# Schematic__2024_schema_2024-06-13.net
KiCad netlist of a schematic drawn in EasyEDA
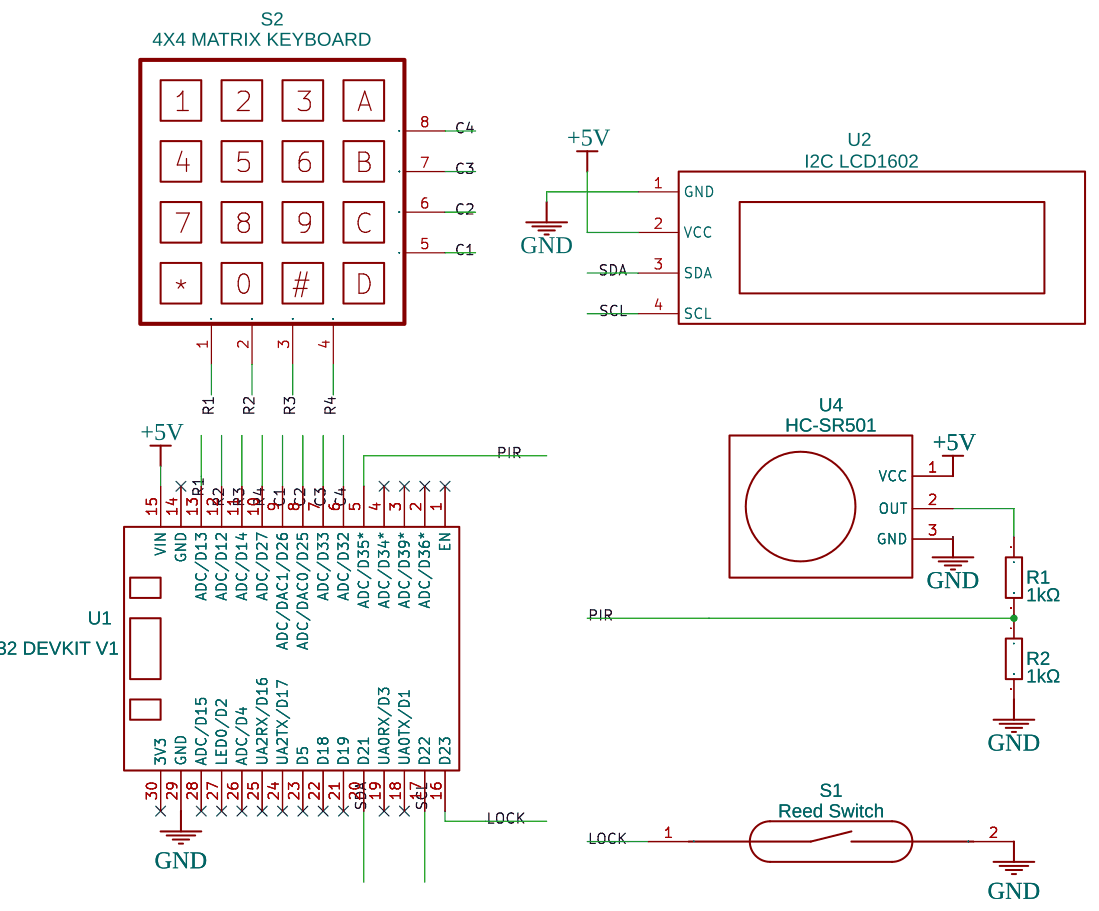
[diagram p0: schematic sheet]

(export (version "E")
  (design (tool "Eeschema 10.0.6"))
  (components
    (comp (ref "R1")
      (value "1kΩ")
      (fields
        (field (name "Manufacturer Part") "MBE04140C1001FC100")
        (field (name "Manufacturer") "VISHAY(威世)")
      )
      (libsource (lib "") (part "MBE04140C1001FC 100"))
    )
    (comp (ref "R2")
      (value "1kΩ")
      (fields
        (field (name "Manufacturer Part") "MBE04140C1001FC100")
        (field (name "Manufacturer") "VISHAY(威世)")
      )
      (libsource (lib "") (part "MBE04140C1001FC 100"))
    )
    (comp (ref "S1") (value "Reed Switch") (libsource (lib "") (part "Reed Switch")))
    (comp (ref "S2") (value "4X4 MATRIX KEYBOARD") (libsource (lib "") (part "4X4 MATRIX KEYBOARD")))
    (comp (ref "U1") (value "ESP32 DEVKIT V1") (libsource (lib "") (part "ESP32 DEVKIT V1")))
    (comp (ref "U2") (value "I2C LCD1602") (libsource (lib "") (part "I2C LCD1602")))
    (comp (ref "U4") (value "HC-SR501") (libsource (lib "") (part "HC-SR501")))
  )
  (nets
    (net (code "1") (name "+5V") (class "Default")
      (node (ref "U1") (pin "15") (pinfunction "VIN_15") (pintype "input"))
      (node (ref "U2") (pin "2") (pinfunction "VCC_2") (pintype "unspecified"))
      (node (ref "U4") (pin "1") (pinfunction "VCC_1") (pintype "unspecified"))
    )
    (net (code "2") (name "/C1") (class "Default")
      (node (ref "S2") (pin "5") (pinfunction "R1_5") (pintype "unspecified"))
      (node (ref "U1") (pin "9") (pinfunction "ADC/DAC1/D26_9") (pintype "bidirectional"))
    )
    (net (code "3") (name "/C2") (class "Default")
      (node (ref "S2") (pin "6") (pinfunction "R2_6") (pintype "unspecified"))
      (node (ref "U1") (pin "8") (pinfunction "ADC/DAC0/D25_8") (pintype "bidirectional"))
    )
    (net (code "4") (name "/C3") (class "Default")
      (node (ref "S2") (pin "7") (pinfunction "R3_7") (pintype "unspecified"))
      (node (ref "U1") (pin "7") (pinfunction "ADC/D33_7") (pintype "bidirectional"))
    )
    (net (code "5") (name "/C4") (class "Default")
      (node (ref "S2") (pin "8") (pinfunction "R4_8") (pintype "unspecified"))
      (node (ref "U1") (pin "6") (pinfunction "ADC/D32_6") (pintype "bidirectional"))
    )
    (net (code "6") (name "/LOCK") (class "Default")
      (node (ref "S1") (pin "1") (pinfunction "1_1") (pintype "unspecified"))
      (node (ref "U1") (pin "16") (pinfunction "D23_16") (pintype "bidirectional"))
    )
    (net (code "7") (name "/PIR") (class "Default")
      (node (ref "R1") (pin "2") (pinfunction "2_2") (pintype "input"))
      (node (ref "R2") (pin "1") (pinfunction "1_1") (pintype "input"))
      (node (ref "U1") (pin "5") (pinfunction "ADC/D35*_5") (pintype "input"))
    )
    (net (code "8") (name "/R1") (class "Default")
      (node (ref "S2") (pin "1") (pinfunction "C1_1") (pintype "unspecified"))
      (node (ref "U1") (pin "13") (pinfunction "ADC/D13_13") (pintype "bidirectional"))
    )
    (net (code "9") (name "/R2") (class "Default")
      (node (ref "S2") (pin "2") (pinfunction "C2_2") (pintype "unspecified"))
      (node (ref "U1") (pin "12") (pinfunction "ADC/D12_12") (pintype "bidirectional"))
    )
    (net (code "10") (name "/R3") (class "Default")
      (node (ref "S2") (pin "3") (pinfunction "C3_3") (pintype "unspecified"))
      (node (ref "U1") (pin "11") (pinfunction "ADC/D14_11") (pintype "bidirectional"))
    )
    (net (code "11") (name "/R4") (class "Default")
      (node (ref "S2") (pin "4") (pinfunction "C4_4") (pintype "unspecified"))
      (node (ref "U1") (pin "10") (pinfunction "ADC/D27_10") (pintype "bidirectional"))
    )
    (net (code "12") (name "/SCL") (class "Default")
      (node (ref "U1") (pin "17") (pinfunction "D22_17") (pintype "bidirectional"))
      (node (ref "U2") (pin "4") (pinfunction "SCL_4") (pintype "unspecified"))
    )
    (net (code "13") (name "/SDA") (class "Default")
      (node (ref "U1") (pin "20") (pinfunction "D21_20") (pintype "bidirectional"))
      (node (ref "U2") (pin "3") (pinfunction "SDA_3") (pintype "unspecified"))
    )
    (net (code "14") (name "GND") (class "Default")
      (node (ref "R2") (pin "2") (pinfunction "2_2") (pintype "input"))
      (node (ref "S1") (pin "2") (pinfunction "2_2") (pintype "unspecified"))
      (node (ref "U1") (pin "29") (pinfunction "GND_29") (pintype "bidirectional"))
      (node (ref "U2") (pin "1") (pinfunction "GND_1") (pintype "unspecified"))
      (node (ref "U4") (pin "3") (pinfunction "GND_3") (pintype "unspecified"))
    )
    (net (code "15") (name "Net-(U4-OUT)") (class "Default")
      (node (ref "R1") (pin "1") (pinfunction "1_1") (pintype "input"))
      (node (ref "U4") (pin "2") (pinfunction "OUT_2") (pintype "unspecified"))
    )
    (net (code "16") (name "unconnected-(U1-3V3-Pad30)") (class "Default")
      (node (ref "U1") (pin "30") (pinfunction "3V3_30") (pintype "bidirectional+no_connect"))
    )
    (net (code "17") (name "unconnected-(U1-ADC{slash}D4-Pad26)") (class "Default")
      (node (ref "U1") (pin "26") (pinfunction "ADC/D4_26") (pintype "bidirectional+no_connect"))
    )
    (net (code "18") (name "unconnected-(U1-ADC{slash}D15-Pad28)") (class "Default")
      (node (ref "U1") (pin "28") (pinfunction "ADC/D15_28") (pintype "bidirectional+no_connect"))
    )
    (net (code "19") (name "unconnected-(U1-ADC{slash}D34*-Pad4)") (class "Default")
      (node (ref "U1") (pin "4") (pinfunction "ADC/D34*_4") (pintype "input+no_connect"))
    )
    (net (code "20") (name "unconnected-(U1-ADC{slash}D36*-Pad2)") (class "Default")
      (node (ref "U1") (pin "2") (pinfunction "ADC/D36*_2") (pintype "input+no_connect"))
    )
    (net (code "21") (name "unconnected-(U1-ADC{slash}D39*-Pad3)") (class "Default")
      (node (ref "U1") (pin "3") (pinfunction "ADC/D39*_3") (pintype "input+no_connect"))
    )
    (net (code "22") (name "unconnected-(U1-D5-Pad23)") (class "Default")
      (node (ref "U1") (pin "23") (pinfunction "D5_23") (pintype "bidirectional+no_connect"))
    )
    (net (code "23") (name "unconnected-(U1-D18-Pad22)") (class "Default")
      (node (ref "U1") (pin "22") (pinfunction "D18_22") (pintype "bidirectional+no_connect"))
    )
    (net (code "24") (name "unconnected-(U1-D19-Pad21)") (class "Default")
      (node (ref "U1") (pin "21") (pinfunction "D19_21") (pintype "bidirectional+no_connect"))
    )
    (net (code "25") (name "unconnected-(U1-EN-Pad1)") (class "Default")
      (node (ref "U1") (pin "1") (pinfunction "EN_1") (pintype "bidirectional+no_connect"))
    )
    (net (code "26") (name "unconnected-(U1-GND-Pad14)") (class "Default")
      (node (ref "U1") (pin "14") (pinfunction "GND_14") (pintype "bidirectional+no_connect"))
    )
    (net (code "27") (name "unconnected-(U1-LED0{slash}D2-Pad27)") (class "Default")
      (node (ref "U1") (pin "27") (pinfunction "LED0/D2_27") (pintype "bidirectional+no_connect"))
    )
    (net (code "28") (name "unconnected-(U1-UA0RX{slash}D3-Pad19)") (class "Default")
      (node (ref "U1") (pin "19") (pinfunction "UA0RX/D3_19") (pintype "bidirectional+no_connect"))
    )
    (net (code "29") (name "unconnected-(U1-UA0TX{slash}D1-Pad18)") (class "Default")
      (node (ref "U1") (pin "18") (pinfunction "UA0TX/D1_18") (pintype "bidirectional+no_connect"))
    )
    (net (code "30") (name "unconnected-(U1-UA2RX{slash}D16-Pad25)") (class "Default")
      (node (ref "U1") (pin "25") (pinfunction "UA2RX/D16_25") (pintype "bidirectional+no_connect"))
    )
    (net (code "31") (name "unconnected-(U1-UA2TX{slash}D17-Pad24)") (class "Default")
      (node (ref "U1") (pin "24") (pinfunction "UA2TX/D17_24") (pintype "bidirectional+no_connect"))
    )
  )
)
